# PWR_TPS65270.net
KiCad netlist of a schematic drawn in Altium Designer
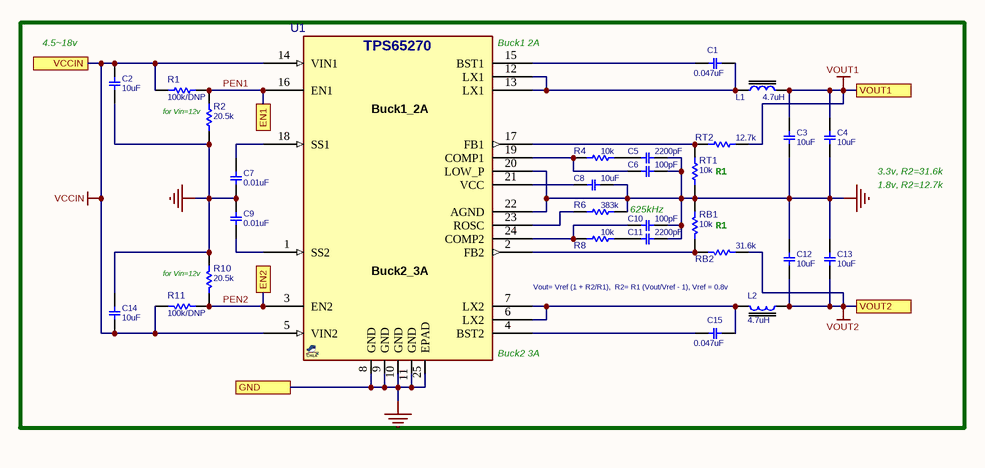
[diagram p0: PWR_TPS65270.SchDoc]

(export (version "E")
  (design (tool "Eeschema 10.0.6"))
  (components
    (comp (ref "C1")
      (value "0.047uF")
      (footprint "C0402")
      (description "CAP, MLCC")
      (fields (field (name "MANF") "Murata"))
      (libsource (lib "passive_mlcc_smd") (part "CAP_SMD_MLCC_100n50V"))
    )
    (comp (ref "C2")
      (value "10uF")
      (footprint "C0603")
      (description "CAP, MLCC")
      (fields (field (name "MANF") "Samsung"))
      (libsource (lib "passive_smd") (part "CAP_SMD_MLCC"))
    )
    (comp (ref "C3")
      (value "10uF")
      (footprint "C0603")
      (description "CAP, MLCC")
      (fields (field (name "MANF") "Samsung"))
      (libsource (lib "passive_smd") (part "CAP_SMD_MLCC"))
    )
    (comp (ref "C4")
      (value "10uF")
      (footprint "C0603")
      (description "CAP, MLCC")
      (fields (field (name "MANF") "Samsung"))
      (libsource (lib "passive_smd") (part "CAP_SMD_MLCC"))
    )
    (comp (ref "C5")
      (value "2200pF")
      (footprint "C0402")
      (description "CAP, MLCC, 0402C")
      (fields (field (name "MANF") "Murata"))
      (libsource (lib "passive_mlcc_smd") (part "CAP_SMD_MLCC_100n50V"))
    )
    (comp (ref "C6")
      (value "100pF")
      (footprint "C0402")
      (description "CAP, MLCC, 0402C")
      (fields (field (name "MANF") "Murata"))
      (libsource (lib "passive_mlcc_smd") (part "CAP_SMD_MLCC_100n50V"))
    )
    (comp (ref "C7")
      (value "0.01uF")
      (footprint "C0402")
      (description "CAP, MLCC, 0402C")
      (fields (field (name "MANF") "Murata"))
      (libsource (lib "passive_mlcc_smd") (part "CAP_SMD_MLCC_100n50V"))
    )
    (comp (ref "C8")
      (value "10uF")
      (footprint "C0603")
      (description "CAP, MLCC")
      (fields (field (name "MANF") "Samsung"))
      (libsource (lib "passive_smd") (part "CAP_SMD_MLCC"))
    )
    (comp (ref "C9")
      (value "0.01uF")
      (footprint "C0402")
      (description "CAP, MLCC, 0402C")
      (fields (field (name "MANF") "Murata"))
      (libsource (lib "passive_mlcc_smd") (part "CAP_SMD_MLCC_100n50V"))
    )
    (comp (ref "C10")
      (value "100pF")
      (footprint "C0402")
      (description "CAP, MLCC, 0402C")
      (fields (field (name "MANF") "Murata"))
      (libsource (lib "passive_mlcc_smd") (part "CAP_SMD_MLCC_100n50V"))
    )
    (comp (ref "C11")
      (value "2200pF")
      (footprint "C0402")
      (description "CAP, MLCC, 0402C")
      (fields (field (name "MANF") "Murata"))
      (libsource (lib "passive_mlcc_smd") (part "CAP_SMD_MLCC_100n50V"))
    )
    (comp (ref "C12")
      (value "10uF")
      (footprint "C0603")
      (description "CAP, MLCC")
      (fields (field (name "MANF") "Samsung"))
      (libsource (lib "passive_smd") (part "CAP_SMD_MLCC"))
    )
    (comp (ref "C13")
      (value "10uF")
      (footprint "C0603")
      (description "CAP, MLCC")
      (fields (field (name "MANF") "Samsung"))
      (libsource (lib "passive_smd") (part "CAP_SMD_MLCC"))
    )
    (comp (ref "C14")
      (value "10uF")
      (footprint "C0603")
      (description "CAP, MLCC")
      (fields (field (name "MANF") "Samsung"))
      (libsource (lib "passive_smd") (part "CAP_SMD_MLCC"))
    )
    (comp (ref "C15")
      (value "0.047uF")
      (footprint "C0402")
      (description "CAP, MLCC")
      (fields (field (name "MANF") "Murata"))
      (libsource (lib "passive_mlcc_smd") (part "CAP_SMD_MLCC_100n50V"))
    )
    (comp (ref "L1")
      (value "4.7uH")
      (footprint "L_6")
      (description "INDUCTOR")
      (fields (field (name "MANF") "Vishay") (field (name "MANF_P#") "VLS6045EX-4R7M"))
      (libsource (lib "") (part "IND_SMD_2.2uH_4A_1"))
    )
    (comp (ref "L2")
      (value "4.7uH")
      (footprint "L_6")
      (description "INDUCTOR")
      (fields (field (name "MANF") "Vishay") (field (name "MANF_P#") "VLS6045EX-4R7M"))
      (libsource (lib "chila_passive") (part "IND_SMD_2.2uH_4A"))
    )
    (comp (ref "R1")
      (value "100k/DNP")
      (footprint "R0402")
      (description "RESISTOR, SMD, 20K, 0402")
      (fields (field (name "MANF") "KOA SPEER") (field (name "MANF_P#") "RK73Z1ETTP"))
      (libsource (lib "chila_passive") (part "RES_SMD"))
    )
    (comp (ref "R2")
      (value "20.5k")
      (footprint "R0402")
      (description "RESISTOR, SMD, 20K, 0402")
      (fields (field (name "MANF") "KOA SPEER") (field (name "MANF_P#") "RK73Z1ETTP"))
      (libsource (lib "chila_passive") (part "RES_SMD"))
    )
    (comp (ref "R4")
      (value "10k")
      (footprint "R0402")
      (description "RESISTOR, SMD, 20K, 0402")
      (fields (field (name "MANF") "Yageo") (field (name "MANF_P#") "RK73H1ETTP2002F"))
      (libsource (lib "chila_passive") (part "RES_SMD"))
    )
    (comp (ref "R6")
      (value "383k")
      (footprint "R0402")
      (description "RESISTOR, SMD, 20K, 0402")
      (fields (field (name "MANF") "Yageo") (field (name "MANF_P#") "RK73H1ETTP2002F"))
      (libsource (lib "chila_passive") (part "RES_SMD"))
    )
    (comp (ref "R8")
      (value "10k")
      (footprint "R0402")
      (description "RESISTOR, SMD, 20K, 0402")
      (fields (field (name "MANF") "Yageo") (field (name "MANF_P#") "RK73H1ETTP2002F"))
      (libsource (lib "chila_passive") (part "RES_SMD"))
    )
    (comp (ref "R10")
      (value "20.5k")
      (footprint "R0402")
      (description "RESISTOR, SMD, 20K, 0402")
      (fields (field (name "MANF") "KOA SPEER") (field (name "MANF_P#") "RK73Z1ETTP"))
      (libsource (lib "chila_passive") (part "RES_SMD"))
    )
    (comp (ref "R11")
      (value "100k/DNP")
      (footprint "R0402")
      (description "RESISTOR, SMD, 20K, 0402")
      (fields (field (name "MANF") "KOA SPEER") (field (name "MANF_P#") "RK73Z1ETTP"))
      (libsource (lib "chila_passive") (part "RES_SMD"))
    )
    (comp (ref "RB1")
      (value "10k")
      (footprint "R0402")
      (description "RESISTOR, SMD, 20K, 0402")
      (fields (field (name "MANF") "Yageo") (field (name "MANF_P#") "RK73H1ETTP2002F"))
      (libsource (lib "chila_passive") (part "RES_SMD"))
    )
    (comp (ref "RB2")
      (value "31.6k")
      (footprint "R0402")
      (description "RESISTOR, SMD, 20K, 0402")
      (fields (field (name "MANF") "Yageo") (field (name "MANF_P#") "RK73H1ETTP2002F"))
      (libsource (lib "chila_passive") (part "RES_SMD"))
    )
    (comp (ref "RT1")
      (value "10k")
      (footprint "R0402")
      (description "RESISTOR, SMD, 20K, 0402")
      (fields (field (name "MANF") "Yageo") (field (name "MANF_P#") "RK73H1ETTP2002F"))
      (libsource (lib "chila_passive") (part "RES_SMD"))
    )
    (comp (ref "RT2")
      (value "12.7k")
      (footprint "R0402")
      (description "RESISTOR, SMD, 20K, 0402")
      (fields (field (name "MANF") "Yageo") (field (name "MANF_P#") "RK73H1ETTP2002F"))
      (libsource (lib "chila_passive") (part "RES_SMD"))
    )
    (comp (ref "U1")
      (value "TPS65270")
      (footprint "QFN50_24T")
      (description "REG, Switching, Buck, Dual 2A/3A, ADJ, 1.4MHz, 4.5~18VIN, QFN-24")
      (fields (field (name "MANF") "Analog Devices") (field (name "MANF_P#") "TPS65270RGE"))
      (libsource (lib "TPS65270") (part "VREG_TPS65270_QFN24"))
    )
  )
  (nets
    (net (code "1") (name "/PEN1") (class "Default")
      (node (ref "R1") (pin "2") (pinfunction "2_2") (pintype "passive"))
      (node (ref "R2") (pin "2") (pinfunction "2_2") (pintype "passive"))
      (node (ref "U1") (pin "16") (pinfunction "EN1_16") (pintype "passive"))
    )
    (net (code "2") (name "/PEN2") (class "Default")
      (node (ref "R10") (pin "2") (pinfunction "2_2") (pintype "passive"))
      (node (ref "R11") (pin "2") (pinfunction "2_2") (pintype "passive"))
      (node (ref "U1") (pin "3") (pinfunction "EN2_3") (pintype "passive"))
    )
    (net (code "3") (name "GND") (class "Default")
      (node (ref "C10") (pin "2") (pinfunction "2_2") (pintype "passive"))
      (node (ref "C11") (pin "2") (pinfunction "2_2") (pintype "passive"))
      (node (ref "C12") (pin "1") (pinfunction "1_1") (pintype "passive"))
      (node (ref "C13") (pin "1") (pinfunction "1_1") (pintype "passive"))
      (node (ref "C14") (pin "1") (pinfunction "1_1") (pintype "passive"))
      (node (ref "C2") (pin "1") (pinfunction "1_1") (pintype "passive"))
      (node (ref "C3") (pin "1") (pinfunction "1_1") (pintype "passive"))
      (node (ref "C4") (pin "1") (pinfunction "1_1") (pintype "passive"))
      (node (ref "C5") (pin "2") (pinfunction "2_2") (pintype "passive"))
      (node (ref "C6") (pin "2") (pinfunction "2_2") (pintype "passive"))
      (node (ref "C7") (pin "2") (pinfunction "2_2") (pintype "passive"))
      (node (ref "C8") (pin "1") (pinfunction "1_1") (pintype "passive"))
      (node (ref "C9") (pin "1") (pinfunction "1_1") (pintype "passive"))
      (node (ref "R10") (pin "1") (pinfunction "1_1") (pintype "passive"))
      (node (ref "R2") (pin "1") (pinfunction "1_1") (pintype "passive"))
      (node (ref "R6") (pin "2") (pinfunction "2_2") (pintype "passive"))
      (node (ref "RB1") (pin "2") (pinfunction "2_2") (pintype "passive"))
      (node (ref "RT1") (pin "2") (pinfunction "2_2") (pintype "passive"))
      (node (ref "U1") (pin "10") (pinfunction "GND_10") (pintype "power_in"))
      (node (ref "U1") (pin "11") (pinfunction "GND_11") (pintype "power_in"))
      (node (ref "U1") (pin "20") (pinfunction "LOW_P_20") (pintype "passive"))
      (node (ref "U1") (pin "22") (pinfunction "AGND_22") (pintype "power_in"))
      (node (ref "U1") (pin "25") (pinfunction "EPAD_25") (pintype "power_in"))
      (node (ref "U1") (pin "8") (pinfunction "GND_8") (pintype "power_in"))
      (node (ref "U1") (pin "9") (pinfunction "GND_9") (pintype "power_in"))
    )
    (net (code "4") (name "Net-(C1-Pad2)") (class "Default")
      (node (ref "C1") (pin "2") (pinfunction "2_2") (pintype "passive"))
      (node (ref "L1") (pin "1") (pinfunction "1_1") (pintype "passive"))
      (node (ref "U1") (pin "12") (pinfunction "LX1_12") (pintype "passive"))
      (node (ref "U1") (pin "13") (pinfunction "LX1_13") (pintype "passive"))
    )
    (net (code "5") (name "Net-(C5-Pad1)") (class "Default")
      (node (ref "C5") (pin "1") (pinfunction "1_1") (pintype "passive"))
      (node (ref "R4") (pin "2") (pinfunction "2_2") (pintype "passive"))
    )
    (net (code "6") (name "Net-(C11-Pad1)") (class "Default")
      (node (ref "C11") (pin "1") (pinfunction "1_1") (pintype "passive"))
      (node (ref "R8") (pin "2") (pinfunction "2_2") (pintype "passive"))
    )
    (net (code "7") (name "Net-(C15-Pad2)") (class "Default")
      (node (ref "C15") (pin "2") (pinfunction "2_2") (pintype "passive"))
      (node (ref "L2") (pin "1") (pinfunction "1_1") (pintype "passive"))
      (node (ref "U1") (pin "6") (pinfunction "LX2_6") (pintype "passive"))
      (node (ref "U1") (pin "7") (pinfunction "LX2_7") (pintype "passive"))
    )
    (net (code "8") (name "Net-(U1-BST1)") (class "Default")
      (node (ref "C1") (pin "1") (pinfunction "1_1") (pintype "passive"))
      (node (ref "U1") (pin "15") (pinfunction "BST1_15") (pintype "passive"))
    )
    (net (code "9") (name "Net-(U1-BST2)") (class "Default")
      (node (ref "C15") (pin "1") (pinfunction "1_1") (pintype "passive"))
      (node (ref "U1") (pin "4") (pinfunction "BST2_4") (pintype "passive"))
    )
    (net (code "10") (name "Net-(U1-COMP1)") (class "Default")
      (node (ref "C6") (pin "1") (pinfunction "1_1") (pintype "passive"))
      (node (ref "R4") (pin "1") (pinfunction "1_1") (pintype "passive"))
      (node (ref "U1") (pin "19") (pinfunction "COMP1_19") (pintype "passive"))
    )
    (net (code "11") (name "Net-(U1-COMP2)") (class "Default")
      (node (ref "C10") (pin "1") (pinfunction "1_1") (pintype "passive"))
      (node (ref "R8") (pin "1") (pinfunction "1_1") (pintype "passive"))
      (node (ref "U1") (pin "24") (pinfunction "COMP2_24") (pintype "passive"))
    )
    (net (code "12") (name "Net-(U1-FB1)") (class "Default")
      (node (ref "RT1") (pin "1") (pinfunction "1_1") (pintype "passive"))
      (node (ref "RT2") (pin "2") (pinfunction "2_2") (pintype "passive"))
      (node (ref "U1") (pin "17") (pinfunction "FB1_17") (pintype "output"))
    )
    (net (code "13") (name "Net-(U1-FB2)") (class "Default")
      (node (ref "RB1") (pin "1") (pinfunction "1_1") (pintype "passive"))
      (node (ref "RB2") (pin "2") (pinfunction "2_2") (pintype "passive"))
      (node (ref "U1") (pin "2") (pinfunction "FB2_2") (pintype "output"))
    )
    (net (code "14") (name "Net-(U1-ROSC)") (class "Default")
      (node (ref "R6") (pin "1") (pinfunction "1_1") (pintype "passive"))
      (node (ref "U1") (pin "23") (pinfunction "ROSC_23") (pintype "passive"))
    )
    (net (code "15") (name "Net-(U1-SS1)") (class "Default")
      (node (ref "C7") (pin "1") (pinfunction "1_1") (pintype "passive"))
      (node (ref "U1") (pin "18") (pinfunction "SS1_18") (pintype "input"))
    )
    (net (code "16") (name "Net-(U1-SS2)") (class "Default")
      (node (ref "C9") (pin "2") (pinfunction "2_2") (pintype "passive"))
      (node (ref "U1") (pin "1") (pinfunction "SS2_1") (pintype "input"))
    )
    (net (code "17") (name "Net-(U1-VCC)") (class "Default")
      (node (ref "C8") (pin "2") (pinfunction "2_2") (pintype "passive"))
      (node (ref "U1") (pin "21") (pinfunction "VCC_21") (pintype "power_in"))
    )
    (net (code "18") (name "VCCIN") (class "Default")
      (node (ref "C14") (pin "2") (pinfunction "2_2") (pintype "passive"))
      (node (ref "C2") (pin "2") (pinfunction "2_2") (pintype "passive"))
      (node (ref "R1") (pin "1") (pinfunction "1_1") (pintype "passive"))
      (node (ref "R11") (pin "1") (pinfunction "1_1") (pintype "passive"))
      (node (ref "U1") (pin "14") (pinfunction "VIN1_14") (pintype "input"))
      (node (ref "U1") (pin "5") (pinfunction "VIN2_5") (pintype "input"))
    )
    (net (code "19") (name "VOUT1") (class "Default")
      (node (ref "C3") (pin "2") (pinfunction "2_2") (pintype "passive"))
      (node (ref "C4") (pin "2") (pinfunction "2_2") (pintype "passive"))
      (node (ref "L1") (pin "2") (pinfunction "2_2") (pintype "passive"))
      (node (ref "RT2") (pin "1") (pinfunction "1_1") (pintype "passive"))
    )
    (net (code "20") (name "VOUT2") (class "Default")
      (node (ref "C12") (pin "2") (pinfunction "2_2") (pintype "passive"))
      (node (ref "C13") (pin "2") (pinfunction "2_2") (pintype "passive"))
      (node (ref "L2") (pin "2") (pinfunction "2_2") (pintype "passive"))
      (node (ref "RB2") (pin "1") (pinfunction "1_1") (pintype "passive"))
    )
  )
)
